# ATTinyX4.net
KiCad netlist of a schematic drawn in EAGLE
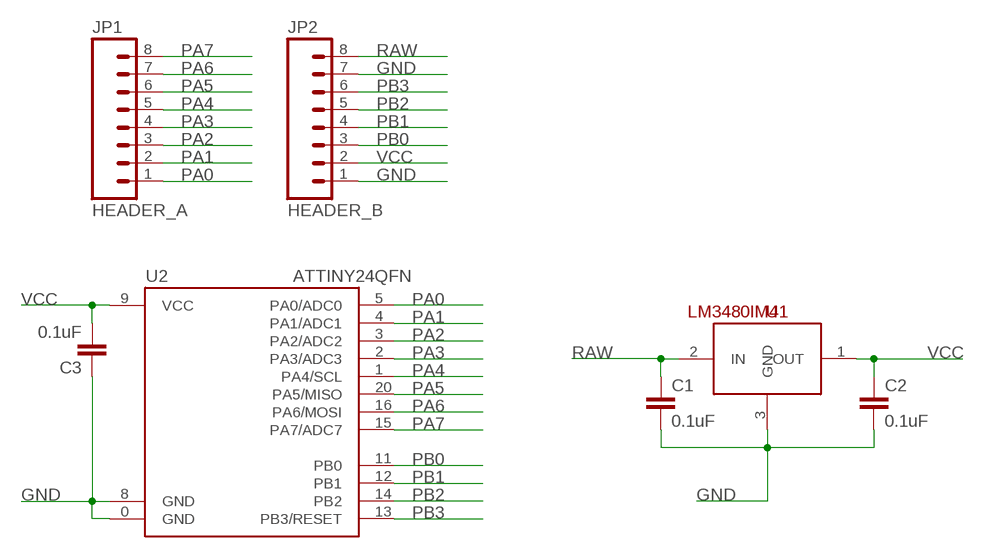
[diagram p0: schematic, sheet 1]

(export (version "E")
  (design (tool "Eeschema 10.0.6"))
  (components
    (comp (ref "C1")
      (value "0.1uF")
      (footprint "eagle-import:0603-CAP")
      (libsource (lib "eagle-import") (part "CAP0603-CAP"))
    )
    (comp (ref "C2")
      (value "0.1uF")
      (footprint "eagle-import:0603-CAP")
      (libsource (lib "eagle-import") (part "CAP0603-CAP"))
    )
    (comp (ref "C3")
      (value "0.1uF")
      (footprint "eagle-import:0603-CAP")
      (libsource (lib "eagle-import") (part "CAP0603-CAP"))
    )
    (comp (ref "JP1")
      (value "HEADER_A")
      (footprint "eagle-import:1X08")
      (libsource (lib "eagle-import") (part "M081X08"))
    )
    (comp (ref "JP2")
      (value "HEADER_B")
      (footprint "eagle-import:1X08")
      (libsource (lib "eagle-import") (part "M081X08"))
    )
    (comp (ref "U1")
      (value "LM3480IM4")
      (footprint "eagle-import:SOT23-3")
      (libsource (lib "eagle-import") (part "LM3480IM4"))
    )
    (comp (ref "U2")
      (value "ATTINY24QFN")
      (footprint "eagle-import:QFN20")
      (libsource (lib "eagle-import") (part "ATTINY24QFN"))
    )
  )
  (nets
    (net (code "1") (name "/GND") (class "Default")
      (node (ref "C1") (pin "2") (pinfunction "2_2") (pintype "passive"))
      (node (ref "C2") (pin "2") (pinfunction "2_2") (pintype "passive"))
      (node (ref "C3") (pin "1") (pinfunction "1_1") (pintype "passive"))
      (node (ref "JP2") (pin "1") (pinfunction "1_1") (pintype "passive"))
      (node (ref "JP2") (pin "7") (pinfunction "7_7") (pintype "passive"))
      (node (ref "U1") (pin "3") (pinfunction "GND_3") (pintype "bidirectional"))
      (node (ref "U2") (pin "0") (pinfunction "GND_0") (pintype "bidirectional"))
      (node (ref "U2") (pin "8") (pinfunction "GND_8") (pintype "bidirectional"))
    )
    (net (code "2") (name "/PA0") (class "Default")
      (node (ref "JP1") (pin "1") (pinfunction "1_1") (pintype "passive"))
      (node (ref "U2") (pin "5") (pinfunction "PA0/ADC0_5") (pintype "bidirectional"))
    )
    (net (code "3") (name "/PA1") (class "Default")
      (node (ref "JP1") (pin "2") (pinfunction "2_2") (pintype "passive"))
      (node (ref "U2") (pin "4") (pinfunction "PA1/ADC1_4") (pintype "bidirectional"))
    )
    (net (code "4") (name "/PA2") (class "Default")
      (node (ref "JP1") (pin "3") (pinfunction "3_3") (pintype "passive"))
      (node (ref "U2") (pin "3") (pinfunction "PA2/ADC2_3") (pintype "bidirectional"))
    )
    (net (code "5") (name "/PA3") (class "Default")
      (node (ref "JP1") (pin "4") (pinfunction "4_4") (pintype "passive"))
      (node (ref "U2") (pin "2") (pinfunction "PA3/ADC3_2") (pintype "bidirectional"))
    )
    (net (code "6") (name "/PA4") (class "Default")
      (node (ref "JP1") (pin "5") (pinfunction "5_5") (pintype "passive"))
      (node (ref "U2") (pin "1") (pinfunction "PA4/SCL_1") (pintype "bidirectional"))
    )
    (net (code "7") (name "/PA5") (class "Default")
      (node (ref "JP1") (pin "6") (pinfunction "6_6") (pintype "passive"))
      (node (ref "U2") (pin "20") (pinfunction "PA5/MISO_20") (pintype "bidirectional"))
    )
    (net (code "8") (name "/PA6") (class "Default")
      (node (ref "JP1") (pin "7") (pinfunction "7_7") (pintype "passive"))
      (node (ref "U2") (pin "16") (pinfunction "PA6/MOSI_16") (pintype "bidirectional"))
    )
    (net (code "9") (name "/PA7") (class "Default")
      (node (ref "JP1") (pin "8") (pinfunction "8_8") (pintype "passive"))
      (node (ref "U2") (pin "15") (pinfunction "PA7/ADC7_15") (pintype "bidirectional"))
    )
    (net (code "10") (name "/PB0") (class "Default")
      (node (ref "JP2") (pin "3") (pinfunction "3_3") (pintype "passive"))
      (node (ref "U2") (pin "11") (pinfunction "PB0_11") (pintype "bidirectional"))
    )
    (net (code "11") (name "/PB1") (class "Default")
      (node (ref "JP2") (pin "4") (pinfunction "4_4") (pintype "passive"))
      (node (ref "U2") (pin "12") (pinfunction "PB1_12") (pintype "bidirectional"))
    )
    (net (code "12") (name "/PB2") (class "Default")
      (node (ref "JP2") (pin "5") (pinfunction "5_5") (pintype "passive"))
      (node (ref "U2") (pin "14") (pinfunction "PB2_14") (pintype "bidirectional"))
    )
    (net (code "13") (name "/PB3") (class "Default")
      (node (ref "JP2") (pin "6") (pinfunction "6_6") (pintype "passive"))
      (node (ref "U2") (pin "13") (pinfunction "PB3/RESET_13") (pintype "bidirectional"))
    )
    (net (code "14") (name "/RAW") (class "Default")
      (node (ref "C1") (pin "1") (pinfunction "1_1") (pintype "passive"))
      (node (ref "JP2") (pin "8") (pinfunction "8_8") (pintype "passive"))
      (node (ref "U1") (pin "2") (pinfunction "IN_2") (pintype "bidirectional"))
    )
    (net (code "15") (name "/VCC") (class "Default")
      (node (ref "C2") (pin "1") (pinfunction "1_1") (pintype "passive"))
      (node (ref "C3") (pin "2") (pinfunction "2_2") (pintype "passive"))
      (node (ref "JP2") (pin "2") (pinfunction "2_2") (pintype "passive"))
      (node (ref "U1") (pin "1") (pinfunction "OUT_1") (pintype "bidirectional"))
      (node (ref "U2") (pin "9") (pinfunction "VCC_9") (pintype "bidirectional"))
    )
  )
)
